# moduleDHT22.net
KiCad netlist of a schematic drawn in EAGLE
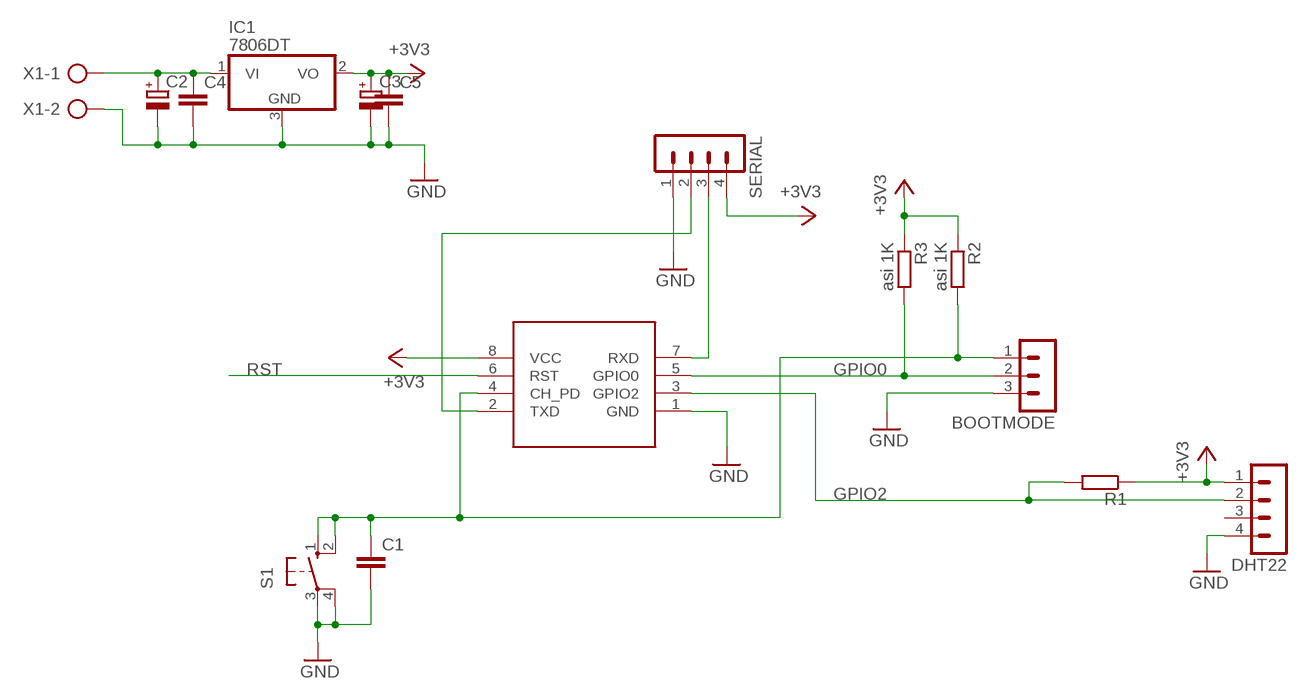
[diagram p0: schematic, sheet 1]

(export (version "E")
  (design (tool "Eeschema 10.0.6"))
  (components
    (comp (ref "BOOTMODE")
      (value "MA03-1")
      (footprint "eagle-import:MA03-1")
      (libsource (lib "eagle-import") (part "MA03-1"))
    )
    (comp (ref "C1")
      (value "C-EUC0603")
      (footprint "eagle-import:C0603")
      (libsource (lib "eagle-import") (part "C-EUC0603"))
    )
    (comp (ref "C2")
      (value "CPOL-EU153CLV-0505")
      (footprint "eagle-import:153CLV-0505")
      (libsource (lib "eagle-import") (part "CPOL-EU153CLV-0505"))
    )
    (comp (ref "C3")
      (value "CPOL-EU153CLV-0505")
      (footprint "eagle-import:153CLV-0505")
      (libsource (lib "eagle-import") (part "CPOL-EU153CLV-0505"))
    )
    (comp (ref "C4")
      (value "C-EUC0603")
      (footprint "eagle-import:C0603")
      (libsource (lib "eagle-import") (part "C-EUC0603"))
    )
    (comp (ref "C5")
      (value "C-EUC0603")
      (footprint "eagle-import:C0603")
      (libsource (lib "eagle-import") (part "C-EUC0603"))
    )
    (comp (ref "DHT22")
      (value "MA04-1")
      (footprint "eagle-import:MA04-1")
      (libsource (lib "eagle-import") (part "MA04-1"))
    )
    (comp (ref "IC1")
      (value "7806DT")
      (footprint "eagle-import:TO252")
      (libsource (lib "eagle-import") (part "78DT06"))
    )
    (comp (ref "R1")
      (value "R-EU_R0603")
      (footprint "eagle-import:R0603")
      (libsource (lib "eagle-import") (part "R-EU_R0603"))
    )
    (comp (ref "R2")
      (value "asi 1K")
      (footprint "eagle-import:R0603")
      (libsource (lib "eagle-import") (part "R-EU_R0603"))
    )
    (comp (ref "R3")
      (value "asi 1K")
      (footprint "eagle-import:R0603")
      (libsource (lib "eagle-import") (part "R-EU_R0603"))
    )
    (comp (ref "S1")
      (value "10-XX")
      (footprint "eagle-import:B3F-10XX")
      (fields (field (name "MPN") "B3F-1000"))
      (libsource (lib "eagle-import") (part "10-XX"))
    )
    (comp (ref "SERIAL")
      (value "MA04-1")
      (footprint "eagle-import:MA04-1")
      (libsource (lib "eagle-import") (part "MA04-1"))
    )
    (comp (ref "U$1")
      (value "ESP8266-01")
      (footprint "eagle-import:ESP8266-01")
      (libsource (lib "eagle-import") (part "ESP8266-01"))
    )
    (comp (ref "X1")
      (value "AK300/2")
      (footprint "eagle-import:AK300_2")
      (libsource (lib "eagle-import") (part "AK300/2"))
    )
  )
  (nets
    (net (code "1") (name "+3V3") (class "Default")
      (node (ref "C3") (pin "+") (pinfunction "+_+") (pintype "passive"))
      (node (ref "C5") (pin "1") (pinfunction "1_1") (pintype "passive"))
      (node (ref "DHT22") (pin "1") (pinfunction "1_1") (pintype "passive"))
      (node (ref "IC1") (pin "2") (pinfunction "VO_2") (pintype "passive"))
      (node (ref "R1") (pin "1") (pinfunction "1_1") (pintype "passive"))
      (node (ref "R2") (pin "1") (pinfunction "1_1") (pintype "passive"))
      (node (ref "R3") (pin "1") (pinfunction "1_1") (pintype "passive"))
      (node (ref "SERIAL") (pin "4") (pinfunction "4_4") (pintype "passive"))
      (node (ref "U$1") (pin "8") (pinfunction "VCC_8") (pintype "bidirectional"))
    )
    (net (code "2") (name "/GPIO0") (class "Default")
      (node (ref "BOOTMODE") (pin "2") (pinfunction "2_2") (pintype "passive"))
      (node (ref "R3") (pin "2") (pinfunction "2_2") (pintype "passive"))
      (node (ref "U$1") (pin "5") (pinfunction "GPIO0_5") (pintype "bidirectional"))
    )
    (net (code "3") (name "/GPIO2") (class "Default")
      (node (ref "DHT22") (pin "2") (pinfunction "2_2") (pintype "passive"))
      (node (ref "R1") (pin "2") (pinfunction "2_2") (pintype "passive"))
      (node (ref "U$1") (pin "3") (pinfunction "GPIO2_3") (pintype "bidirectional"))
    )
    (net (code "4") (name "/RST") (class "Default")
      (node (ref "U$1") (pin "6") (pinfunction "RST_6") (pintype "bidirectional"))
    )
    (net (code "5") (name "GND") (class "Default")
      (node (ref "BOOTMODE") (pin "3") (pinfunction "3_3") (pintype "passive"))
      (node (ref "C1") (pin "2") (pinfunction "2_2") (pintype "passive"))
      (node (ref "C2") (pin "-") (pinfunction "-_-") (pintype "passive"))
      (node (ref "C3") (pin "-") (pinfunction "-_-") (pintype "passive"))
      (node (ref "C4") (pin "2") (pinfunction "2_2") (pintype "passive"))
      (node (ref "C5") (pin "2") (pinfunction "2_2") (pintype "passive"))
      (node (ref "DHT22") (pin "4") (pinfunction "4_4") (pintype "passive"))
      (node (ref "IC1") (pin "3") (pinfunction "GND_3") (pintype "passive"))
      (node (ref "S1") (pin "3") (pinfunction "P_3") (pintype "passive"))
      (node (ref "S1") (pin "4") (pinfunction "P1_4") (pintype "passive"))
      (node (ref "SERIAL") (pin "1") (pinfunction "1_1") (pintype "passive"))
      (node (ref "U$1") (pin "1") (pinfunction "GND_1") (pintype "bidirectional"))
      (node (ref "X1") (pin "2") (pinfunction "KL_2") (pintype "passive"))
    )
    (net (code "6") (name "Net-(IC1-VI)") (class "Default")
      (node (ref "C2") (pin "+") (pinfunction "+_+") (pintype "passive"))
      (node (ref "C4") (pin "1") (pinfunction "1_1") (pintype "passive"))
      (node (ref "IC1") (pin "1") (pinfunction "VI_1") (pintype "input"))
      (node (ref "X1") (pin "1") (pinfunction "KL_1") (pintype "passive"))
    )
    (net (code "7") (name "Net-(S1-S)") (class "Default")
      (node (ref "BOOTMODE") (pin "1") (pinfunction "1_1") (pintype "passive"))
      (node (ref "C1") (pin "1") (pinfunction "1_1") (pintype "passive"))
      (node (ref "R2") (pin "2") (pinfunction "2_2") (pintype "passive"))
      (node (ref "S1") (pin "1") (pinfunction "S_1") (pintype "passive"))
      (node (ref "S1") (pin "2") (pinfunction "S1_2") (pintype "passive"))
      (node (ref "U$1") (pin "4") (pinfunction "CH_PD_4") (pintype "bidirectional"))
    )
    (net (code "8") (name "Net-(U$1-RXD)") (class "Default")
      (node (ref "SERIAL") (pin "3") (pinfunction "3_3") (pintype "passive"))
      (node (ref "U$1") (pin "7") (pinfunction "RXD_7") (pintype "bidirectional"))
    )
    (net (code "9") (name "Net-(U$1-TXD)") (class "Default")
      (node (ref "SERIAL") (pin "2") (pinfunction "2_2") (pintype "passive"))
      (node (ref "U$1") (pin "2") (pinfunction "TXD_2") (pintype "bidirectional"))
    )
    (net (code "10") (name "unconnected-(DHT22-Pad3)") (class "Default")
      (node (ref "DHT22") (pin "3") (pinfunction "3_3") (pintype "passive"))
    )
  )
)
